# MLX90614_Break_Board_SCH.net
KiCad netlist of a schematic drawn in EAGLE
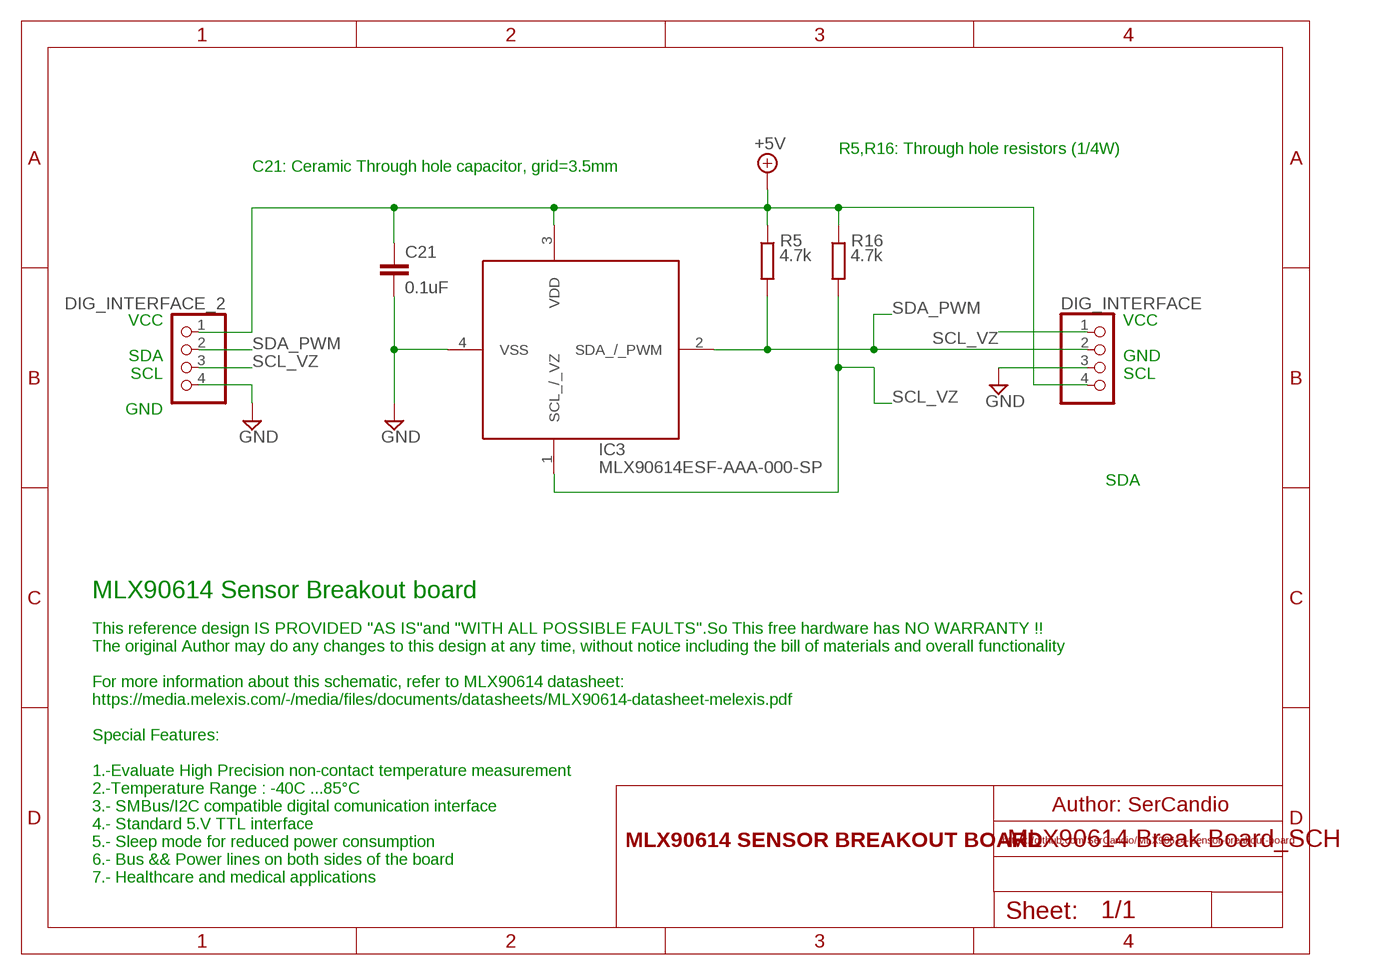
[diagram p0: schematic, sheet 1]

(export (version "E")
  (design (tool "Eeschema 10.0.6"))
  (components
    (comp (ref "C21")
      (value "0.1uF")
      (footprint "eagle-import:C025-025X050")
      (libsource (lib "eagle-import") (part "C-EU025-025X050"))
    )
    (comp (ref "DIG_INTERFACE")
      (value "PINHD-1X4/90")
      (footprint "eagle-import:1X04_90")
      (libsource (lib "eagle-import") (part "PINHD-1X4/90"))
    )
    (comp (ref "DIG_INTERFACE_2")
      (value "PINHD-1X4/90")
      (footprint "eagle-import:1X04_90")
      (libsource (lib "eagle-import") (part "PINHD-1X4/90"))
    )
    (comp (ref "IC3")
      (value "MLX90614ESF-AAA-000-SP")
      (footprint "eagle-import:MLX90614ESFAAA000SP")
      (fields (field (name "MOUSER_PART_NUMBER") "482-90614ESFAAA000SP"))
      (libsource (lib "eagle-import") (part "MLX90614ESF-AAA-000-SP"))
    )
    (comp (ref "R5")
      (value "4.7k")
      (footprint "eagle-import:0207_10")
      (libsource (lib "eagle-import") (part "R-EU_0207/10"))
    )
    (comp (ref "R16")
      (value "4.7k")
      (footprint "eagle-import:0207_10")
      (libsource (lib "eagle-import") (part "R-EU_0207/10"))
    )
  )
  (nets
    (net (code "1") (name "+5V") (class "Default")
      (node (ref "C21") (pin "1") (pinfunction "1_1") (pintype "passive"))
      (node (ref "DIG_INTERFACE") (pin "4") (pinfunction "4_4") (pintype "passive"))
      (node (ref "DIG_INTERFACE_2") (pin "1") (pinfunction "1_1") (pintype "passive"))
      (node (ref "IC3") (pin "3") (pinfunction "VDD_3") (pintype "bidirectional"))
      (node (ref "R16") (pin "1") (pinfunction "1_1") (pintype "passive"))
      (node (ref "R5") (pin "1") (pinfunction "1_1") (pintype "passive"))
    )
    (net (code "2") (name "/SCL_VZ") (class "Default")
      (node (ref "DIG_INTERFACE") (pin "1") (pinfunction "1_1") (pintype "passive"))
      (node (ref "DIG_INTERFACE_2") (pin "3") (pinfunction "3_3") (pintype "passive"))
      (node (ref "IC3") (pin "1") (pinfunction "SCL_/_VZ_1") (pintype "bidirectional"))
      (node (ref "R16") (pin "2") (pinfunction "2_2") (pintype "passive"))
    )
    (net (code "3") (name "/SDA_PWM") (class "Default")
      (node (ref "DIG_INTERFACE") (pin "2") (pinfunction "2_2") (pintype "passive"))
      (node (ref "DIG_INTERFACE_2") (pin "2") (pinfunction "2_2") (pintype "passive"))
      (node (ref "IC3") (pin "2") (pinfunction "SDA_/_PWM_2") (pintype "bidirectional"))
      (node (ref "R5") (pin "2") (pinfunction "2_2") (pintype "passive"))
    )
    (net (code "4") (name "GND") (class "Default")
      (node (ref "C21") (pin "2") (pinfunction "2_2") (pintype "passive"))
      (node (ref "DIG_INTERFACE") (pin "3") (pinfunction "3_3") (pintype "passive"))
      (node (ref "DIG_INTERFACE_2") (pin "4") (pinfunction "4_4") (pintype "passive"))
      (node (ref "IC3") (pin "4") (pinfunction "VSS_4") (pintype "bidirectional"))
    )
  )
)
